# RoboSkinRev1.net
KiCad netlist of a schematic drawn in EAGLE
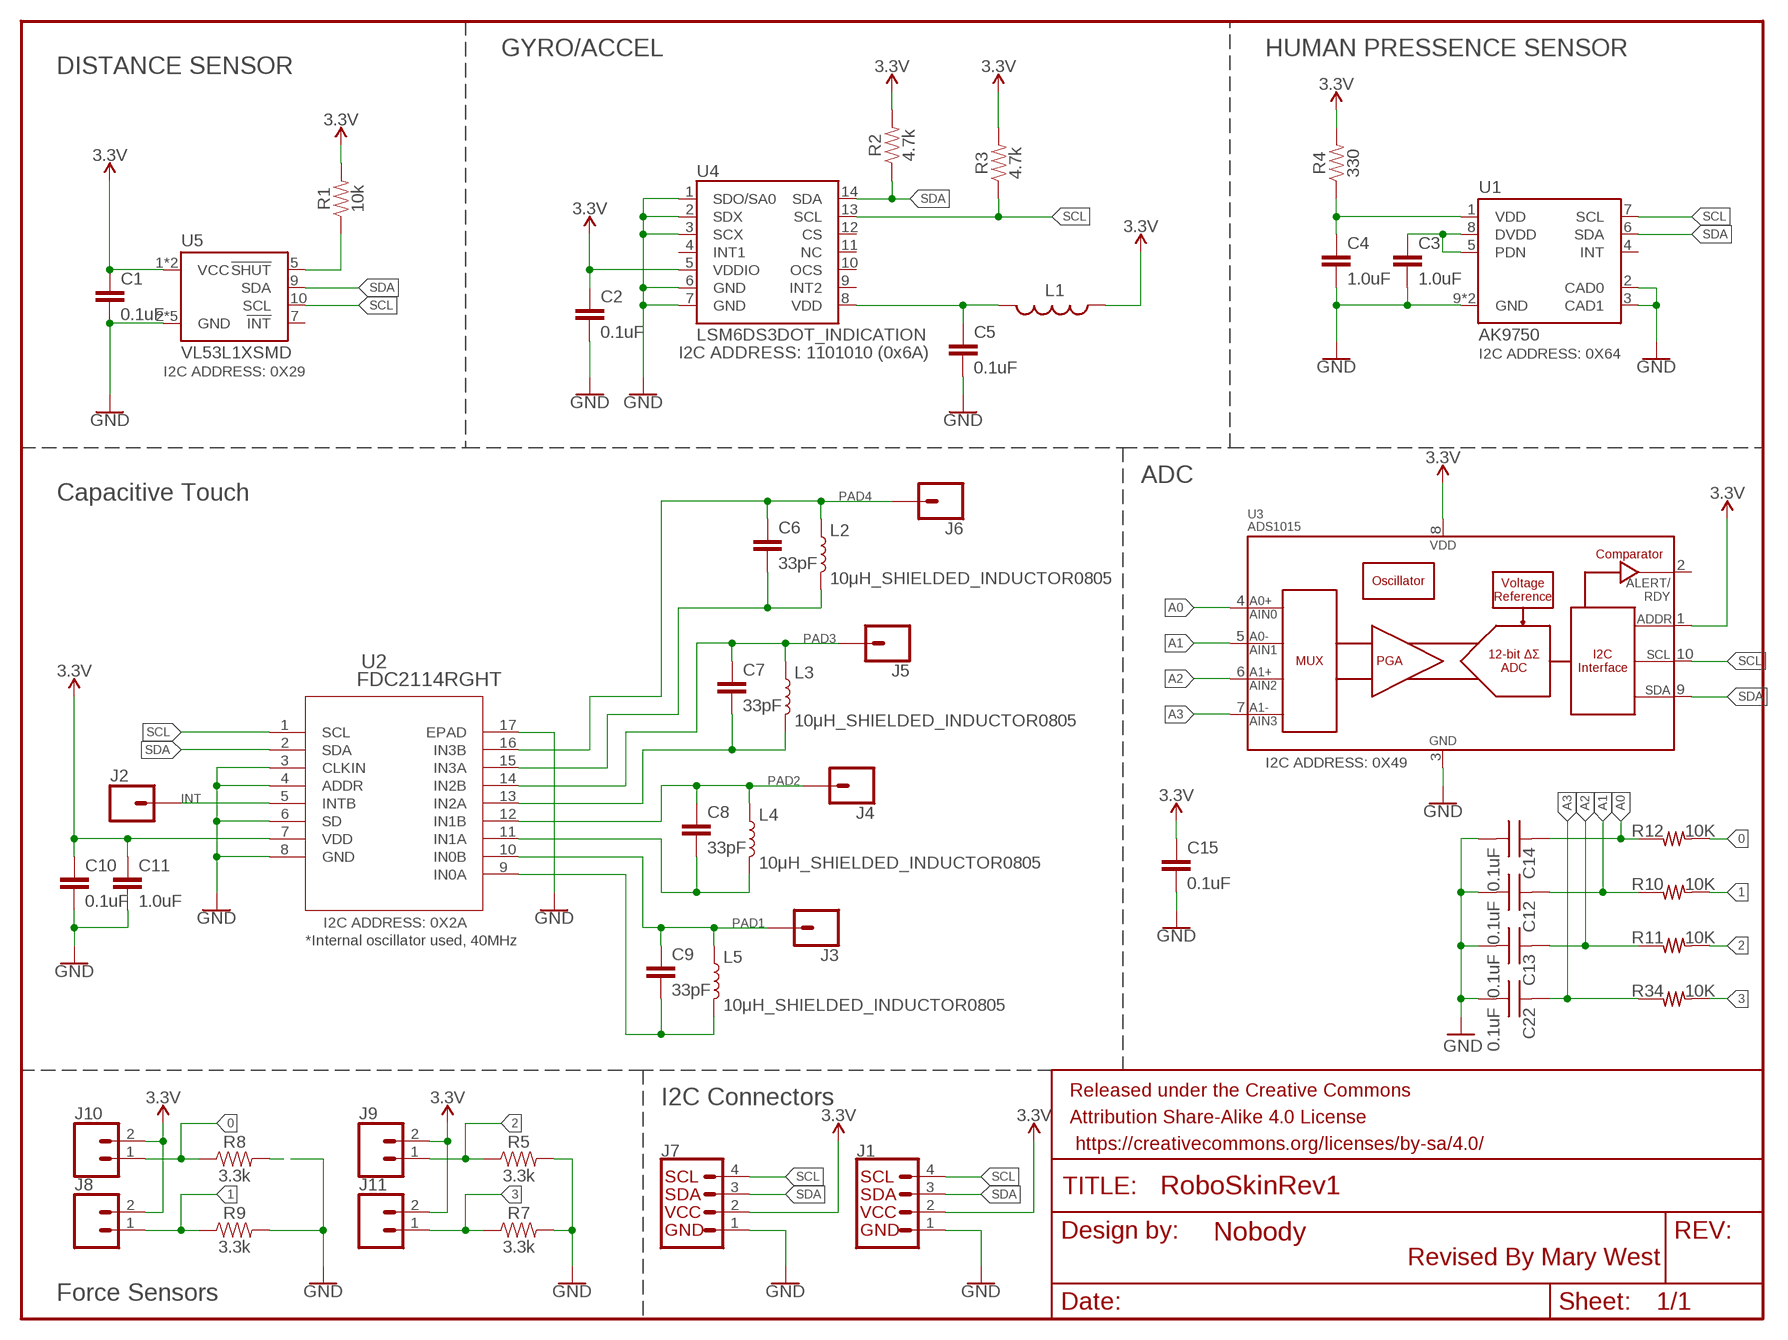
[diagram p0: schematic, sheet 1]

(export (version "E")
  (design (tool "Eeschema 10.0.6"))
  (components
    (comp (ref "C1")
      (value "0.1uF")
      (footprint "eagle-import:0603")
      (libsource (lib "eagle-import") (part "0.1UF-0603-25V-(+80/-20%)"))
    )
    (comp (ref "C2")
      (value "0.1uF")
      (footprint "eagle-import:0603")
      (libsource (lib "eagle-import") (part "0.1UF-0603-25V-(+80/-20%)"))
    )
    (comp (ref "C3")
      (value "1.0uF")
      (footprint "eagle-import:0603")
      (libsource (lib "eagle-import") (part "1.0UF-0603-16V-10%"))
    )
    (comp (ref "C4")
      (value "1.0uF")
      (footprint "eagle-import:0603")
      (libsource (lib "eagle-import") (part "1.0UF-0603-16V-10%"))
    )
    (comp (ref "C5")
      (value "0.1uF")
      (footprint "eagle-import:0603")
      (libsource (lib "eagle-import") (part "0.1UF-0603-25V-(+80/-20%)"))
    )
    (comp (ref "C6")
      (value "33pF")
      (footprint "eagle-import:0603")
      (libsource (lib "eagle-import") (part "33PF-0603-50V-5%"))
    )
    (comp (ref "C7")
      (value "33pF")
      (footprint "eagle-import:0603")
      (libsource (lib "eagle-import") (part "33PF-0603-50V-5%"))
    )
    (comp (ref "C8")
      (value "33pF")
      (footprint "eagle-import:0603")
      (libsource (lib "eagle-import") (part "33PF-0603-50V-5%"))
    )
    (comp (ref "C9")
      (value "33pF")
      (footprint "eagle-import:0603")
      (libsource (lib "eagle-import") (part "33PF-0603-50V-5%"))
    )
    (comp (ref "C10")
      (value "0.1uF")
      (footprint "eagle-import:0603")
      (libsource (lib "eagle-import") (part "0.1UF-0603-25V-(+80/-20%)"))
    )
    (comp (ref "C11")
      (value "1.0uF")
      (footprint "eagle-import:0603")
      (libsource (lib "eagle-import") (part "1.0UF-0603-16V-10%"))
    )
    (comp (ref "C12")
      (value "0.1uF")
      (footprint "eagle-import:0603_SILK")
      (fields (field (name "PARTNO") "GRM188R70J104KA01D"))
      (libsource (lib "eagle-import") (part "CAPACITORC_0603_SILK"))
    )
    (comp (ref "C13")
      (value "0.1uF")
      (footprint "eagle-import:0603_SILK")
      (fields (field (name "PARTNO") "GRM188R70J104KA01D"))
      (libsource (lib "eagle-import") (part "CAPACITORC_0603_SILK"))
    )
    (comp (ref "C14")
      (value "0.1uF")
      (footprint "eagle-import:0603_SILK")
      (fields (field (name "PARTNO") "GRM188R70J104KA01D"))
      (libsource (lib "eagle-import") (part "CAPACITORC_0603_SILK"))
    )
    (comp (ref "C15")
      (value "0.1uF")
      (footprint "eagle-import:0603")
      (libsource (lib "eagle-import") (part "0.1UF-0603-25V-(+80/-20%)"))
    )
    (comp (ref "C22")
      (value "0.1uF")
      (footprint "eagle-import:0603_SILK")
      (fields (field (name "PARTNO") "GRM188R70J104KA01D"))
      (libsource (lib "eagle-import") (part "CAPACITORC_0603_SILK"))
    )
    (comp (ref "FRAME1")
      (value "FRAME-LETTERNO_PACKAGE")
      (footprint "eagle-import:DUMMY")
      (fields (field (name "DESIGNER") "Nobody"))
      (libsource (lib "eagle-import") (part "FRAME-LETTERNO_PACKAGE"))
    )
    (comp (ref "J1")
      (value "QWIIC_CONNECTORJS-1MM")
      (footprint "eagle-import:1X04_1MM_RA")
      (libsource (lib "eagle-import") (part "QWIIC_CONNECTORJS-1MM"))
    )
    (comp (ref "J2")
      (value "CONN_01")
      (footprint "eagle-import:1X01")
      (libsource (lib "eagle-import") (part "CONN_01"))
    )
    (comp (ref "J3")
      (value "CONN_01")
      (footprint "eagle-import:1X01")
      (libsource (lib "eagle-import") (part "CONN_01"))
    )
    (comp (ref "J4")
      (value "CONN_01")
      (footprint "eagle-import:1X01")
      (libsource (lib "eagle-import") (part "CONN_01"))
    )
    (comp (ref "J5")
      (value "CONN_01")
      (footprint "eagle-import:1X01")
      (libsource (lib "eagle-import") (part "CONN_01"))
    )
    (comp (ref "J6")
      (value "CONN_01")
      (footprint "eagle-import:1X01")
      (libsource (lib "eagle-import") (part "CONN_01"))
    )
    (comp (ref "J7")
      (value "QWIIC_CONNECTORJS-1MM")
      (footprint "eagle-import:1X04_1MM_RA")
      (libsource (lib "eagle-import") (part "QWIIC_CONNECTORJS-1MM"))
    )
    (comp (ref "J8")
      (value "CONN_02")
      (footprint "eagle-import:1X02")
      (libsource (lib "eagle-import") (part "CONN_02"))
    )
    (comp (ref "J9")
      (value "CONN_02")
      (footprint "eagle-import:1X02")
      (libsource (lib "eagle-import") (part "CONN_02"))
    )
    (comp (ref "J10")
      (value "CONN_02")
      (footprint "eagle-import:1X02")
      (libsource (lib "eagle-import") (part "CONN_02"))
    )
    (comp (ref "J11")
      (value "CONN_02")
      (footprint "eagle-import:1X02")
      (libsource (lib "eagle-import") (part "CONN_02"))
    )
    (comp (ref "L1")
      (value "RES-07859")
      (footprint "eagle-import:0603")
      (libsource (lib "eagle-import") (part "INDUCTOR30OHM,1.8A"))
    )
    (comp (ref "L2")
      (value "10μH_SHIELDED_INDUCTOR0805")
      (footprint "eagle-import:0805")
      (libsource (lib "eagle-import") (part "10μH_SHIELDED_INDUCTOR0805"))
    )
    (comp (ref "L3")
      (value "10μH_SHIELDED_INDUCTOR0805")
      (footprint "eagle-import:0805")
      (libsource (lib "eagle-import") (part "10μH_SHIELDED_INDUCTOR0805"))
    )
    (comp (ref "L4")
      (value "10μH_SHIELDED_INDUCTOR0805")
      (footprint "eagle-import:0805")
      (libsource (lib "eagle-import") (part "10μH_SHIELDED_INDUCTOR0805"))
    )
    (comp (ref "L5")
      (value "10μH_SHIELDED_INDUCTOR0805")
      (footprint "eagle-import:0805")
      (libsource (lib "eagle-import") (part "10μH_SHIELDED_INDUCTOR0805"))
    )
    (comp (ref "R1")
      (value "10k")
      (footprint "eagle-import:0603")
      (libsource (lib "eagle-import") (part "10KOHM-0603-1/10W-1%"))
    )
    (comp (ref "R2")
      (value "4.7k")
      (footprint "eagle-import:0603")
      (libsource (lib "eagle-import") (part "4.7KOHM-0603-1/10W-1%"))
    )
    (comp (ref "R3")
      (value "4.7k")
      (footprint "eagle-import:0603")
      (libsource (lib "eagle-import") (part "4.7KOHM-0603-1/10W-1%"))
    )
    (comp (ref "R4")
      (value "330")
      (footprint "eagle-import:0603")
      (libsource (lib "eagle-import") (part "330OHM-0603-1/10W-1%"))
    )
    (comp (ref "R5")
      (value "3.3k")
      (footprint "eagle-import:0603")
      (libsource (lib "eagle-import") (part "3.3KOHM-0603-1/10W-1%"))
    )
    (comp (ref "R7")
      (value "3.3k")
      (footprint "eagle-import:0603")
      (libsource (lib "eagle-import") (part "3.3KOHM-0603-1/10W-1%"))
    )
    (comp (ref "R8")
      (value "3.3k")
      (footprint "eagle-import:0603")
      (libsource (lib "eagle-import") (part "3.3KOHM-0603-1/10W-1%"))
    )
    (comp (ref "R9")
      (value "3.3k")
      (footprint "eagle-import:0603")
      (libsource (lib "eagle-import") (part "3.3KOHM-0603-1/10W-1%"))
    )
    (comp (ref "R10")
      (value "10K")
      (footprint "eagle-import:0603_SILK")
      (fields (field (name "PARTNO") "CR0603-FX-1002ELF"))
      (libsource (lib "eagle-import") (part "RESISTORR_0603_SILK"))
    )
    (comp (ref "R11")
      (value "10K")
      (footprint "eagle-import:0603_SILK")
      (fields (field (name "PARTNO") "CR0603-FX-1002ELF"))
      (libsource (lib "eagle-import") (part "RESISTORR_0603_SILK"))
    )
    (comp (ref "R12")
      (value "10K")
      (footprint "eagle-import:0603_SILK")
      (fields (field (name "PARTNO") "CR0603-FX-1002ELF"))
      (libsource (lib "eagle-import") (part "RESISTORR_0603_SILK"))
    )
    (comp (ref "R34")
      (value "10K")
      (footprint "eagle-import:0603_SILK")
      (fields (field (name "PARTNO") "CR0603-FX-1002ELF"))
      (libsource (lib "eagle-import") (part "RESISTORR_0603_SILK"))
    )
    (comp (ref "U1")
      (value "AK9750")
      (footprint "eagle-import:SON10")
      (libsource (lib "eagle-import") (part "AK9750"))
    )
    (comp (ref "U2")
      (value "FDC2114RGHT")
      (footprint "eagle-import:RGH16")
      (fields (field (name "COPYRIGHT") "Copyright (C) 2018 Accelerated Designs. All rights reserved"))
      (libsource (lib "eagle-import") (part "FDC2114RGHT"))
    )
    (comp (ref "U3")
      (value "ADS1015")
      (footprint "eagle-import:MSOP10")
      (libsource (lib "eagle-import") (part "ADS1015"))
    )
    (comp (ref "U4")
      (value "LSM6DS3DOT_INDICATION")
      (footprint "eagle-import:LGA14L_DOT_INDICATOR")
      (libsource (lib "eagle-import") (part "LSM6DS3DOT_INDICATION"))
    )
    (comp (ref "U5")
      (value "VL53L1XSMD")
      (footprint "eagle-import:VL53L1X")
      (libsource (lib "eagle-import") (part "VL53L1XSMD"))
    )
  )
  (nets
    (net (code "1") (name "/INT") (class "Default")
      (node (ref "J2") (pin "1") (pinfunction "1_1") (pintype "passive"))
      (node (ref "U2") (pin "5") (pinfunction "INTB_5") (pintype "output"))
    )
    (net (code "2") (name "/PAD1") (class "Default")
      (node (ref "C9") (pin "1") (pinfunction "1_1") (pintype "passive"))
      (node (ref "J3") (pin "1") (pinfunction "1_1") (pintype "passive"))
      (node (ref "L5") (pin "1") (pinfunction "1_1") (pintype "passive"))
      (node (ref "U2") (pin "10") (pinfunction "IN0B_10") (pintype "input"))
    )
    (net (code "3") (name "/PAD2") (class "Default")
      (node (ref "C8") (pin "1") (pinfunction "1_1") (pintype "passive"))
      (node (ref "J4") (pin "1") (pinfunction "1_1") (pintype "passive"))
      (node (ref "L4") (pin "1") (pinfunction "1_1") (pintype "passive"))
      (node (ref "U2") (pin "12") (pinfunction "IN1B_12") (pintype "input"))
    )
    (net (code "4") (name "/PAD3") (class "Default")
      (node (ref "C7") (pin "1") (pinfunction "1_1") (pintype "passive"))
      (node (ref "J5") (pin "1") (pinfunction "1_1") (pintype "passive"))
      (node (ref "L3") (pin "1") (pinfunction "1_1") (pintype "passive"))
      (node (ref "U2") (pin "14") (pinfunction "IN2B_14") (pintype "input"))
    )
    (net (code "5") (name "/PAD4") (class "Default")
      (node (ref "C6") (pin "1") (pinfunction "1_1") (pintype "passive"))
      (node (ref "J6") (pin "1") (pinfunction "1_1") (pintype "passive"))
      (node (ref "L2") (pin "1") (pinfunction "1_1") (pintype "passive"))
      (node (ref "U2") (pin "16") (pinfunction "IN3B_16") (pintype "input"))
    )
    (net (code "6") (name "0") (class "Default")
      (node (ref "J10") (pin "1") (pinfunction "1_1") (pintype "passive"))
      (node (ref "R12") (pin "P2") (pinfunction "2_P2") (pintype "passive"))
      (node (ref "R8") (pin "1") (pinfunction "1_1") (pintype "passive"))
    )
    (net (code "7") (name "1") (class "Default")
      (node (ref "J8") (pin "1") (pinfunction "1_1") (pintype "passive"))
      (node (ref "R10") (pin "P2") (pinfunction "2_P2") (pintype "passive"))
      (node (ref "R9") (pin "1") (pinfunction "1_1") (pintype "passive"))
    )
    (net (code "8") (name "2") (class "Default")
      (node (ref "J9") (pin "1") (pinfunction "1_1") (pintype "passive"))
      (node (ref "R11") (pin "P2") (pinfunction "2_P2") (pintype "passive"))
      (node (ref "R5") (pin "1") (pinfunction "1_1") (pintype "passive"))
    )
    (net (code "9") (name "3") (class "Default")
      (node (ref "J11") (pin "1") (pinfunction "1_1") (pintype "passive"))
      (node (ref "R34") (pin "P2") (pinfunction "2_P2") (pintype "passive"))
      (node (ref "R7") (pin "1") (pinfunction "1_1") (pintype "passive"))
    )
    (net (code "10") (name "3.3V") (class "Default")
      (node (ref "C1") (pin "1") (pinfunction "1_1") (pintype "passive"))
      (node (ref "C10") (pin "1") (pinfunction "1_1") (pintype "passive"))
      (node (ref "C11") (pin "1") (pinfunction "1_1") (pintype "passive"))
      (node (ref "C15") (pin "1") (pinfunction "1_1") (pintype "passive"))
      (node (ref "C2") (pin "1") (pinfunction "1_1") (pintype "passive"))
      (node (ref "J1") (pin "2") (pinfunction "VCC_2") (pintype "power_in"))
      (node (ref "J10") (pin "2") (pinfunction "2_2") (pintype "passive"))
      (node (ref "J11") (pin "2") (pinfunction "2_2") (pintype "passive"))
      (node (ref "J7") (pin "2") (pinfunction "VCC_2") (pintype "power_in"))
      (node (ref "J8") (pin "2") (pinfunction "2_2") (pintype "passive"))
      (node (ref "J9") (pin "2") (pinfunction "2_2") (pintype "passive"))
      (node (ref "L1") (pin "1") (pinfunction "1_1") (pintype "passive"))
      (node (ref "R1") (pin "2") (pinfunction "2_2") (pintype "passive"))
      (node (ref "R2") (pin "2") (pinfunction "2_2") (pintype "passive"))
      (node (ref "R3") (pin "2") (pinfunction "2_2") (pintype "passive"))
      (node (ref "R4") (pin "2") (pinfunction "2_2") (pintype "passive"))
      (node (ref "U2") (pin "7") (pinfunction "VDD_7") (pintype "power_in"))
      (node (ref "U3") (pin "1") (pinfunction "ADDR_1") (pintype "bidirectional"))
      (node (ref "U3") (pin "8") (pinfunction "VDD_8") (pintype "bidirectional"))
      (node (ref "U4") (pin "5") (pinfunction "VDDIO_5") (pintype "bidirectional"))
      (node (ref "U5") (pin "1") (pinfunction "VCC_1") (pintype "bidirectional"))
      (node (ref "U5") (pin "11") (pinfunction "VCC_11") (pintype "bidirectional"))
    )
    (net (code "11") (name "A0") (class "Default")
      (node (ref "C14") (pin "P1") (pinfunction "1_P1") (pintype "passive"))
      (node (ref "R12") (pin "P1") (pinfunction "1_P1") (pintype "passive"))
      (node (ref "U3") (pin "4") (pinfunction "AIN0_4") (pintype "bidirectional"))
    )
    (net (code "12") (name "A1") (class "Default")
      (node (ref "C12") (pin "P1") (pinfunction "1_P1") (pintype "passive"))
      (node (ref "R10") (pin "P1") (pinfunction "1_P1") (pintype "passive"))
      (node (ref "U3") (pin "5") (pinfunction "AIN1_5") (pintype "bidirectional"))
    )
    (net (code "13") (name "A2") (class "Default")
      (node (ref "C13") (pin "P1") (pinfunction "1_P1") (pintype "passive"))
      (node (ref "R11") (pin "P1") (pinfunction "1_P1") (pintype "passive"))
      (node (ref "U3") (pin "6") (pinfunction "AIN2_6") (pintype "bidirectional"))
    )
    (net (code "14") (name "A3") (class "Default")
      (node (ref "C22") (pin "P1") (pinfunction "1_P1") (pintype "passive"))
      (node (ref "R34") (pin "P1") (pinfunction "1_P1") (pintype "passive"))
      (node (ref "U3") (pin "7") (pinfunction "AIN3_7") (pintype "bidirectional"))
    )
    (net (code "15") (name "GND") (class "Default")
      (node (ref "C1") (pin "2") (pinfunction "2_2") (pintype "passive"))
      (node (ref "C10") (pin "2") (pinfunction "2_2") (pintype "passive"))
      (node (ref "C11") (pin "2") (pinfunction "2_2") (pintype "passive"))
      (node (ref "C12") (pin "P2") (pinfunction "2_P2") (pintype "passive"))
      (node (ref "C13") (pin "P2") (pinfunction "2_P2") (pintype "passive"))
      (node (ref "C14") (pin "P2") (pinfunction "2_P2") (pintype "passive"))
      (node (ref "C15") (pin "2") (pinfunction "2_2") (pintype "passive"))
      (node (ref "C2") (pin "2") (pinfunction "2_2") (pintype "passive"))
      (node (ref "C22") (pin "P2") (pinfunction "2_P2") (pintype "passive"))
      (node (ref "C3") (pin "2") (pinfunction "2_2") (pintype "passive"))
      (node (ref "C4") (pin "2") (pinfunction "2_2") (pintype "passive"))
      (node (ref "C5") (pin "2") (pinfunction "2_2") (pintype "passive"))
      (node (ref "J1") (pin "1") (pinfunction "GND_1") (pintype "power_in"))
      (node (ref "J7") (pin "1") (pinfunction "GND_1") (pintype "power_in"))
      (node (ref "R5") (pin "2") (pinfunction "2_2") (pintype "passive"))
      (node (ref "R7") (pin "2") (pinfunction "2_2") (pintype "passive"))
      (node (ref "R8") (pin "2") (pinfunction "2_2") (pintype "passive"))
      (node (ref "R9") (pin "2") (pinfunction "2_2") (pintype "passive"))
      (node (ref "U1") (pin "10") (pinfunction "GND_10") (pintype "bidirectional"))
      (node (ref "U1") (pin "2") (pinfunction "CAD0_2") (pintype "bidirectional"))
      (node (ref "U1") (pin "3") (pinfunction "CAD1_3") (pintype "bidirectional"))
      (node (ref "U1") (pin "9") (pinfunction "GND_9") (pintype "bidirectional"))
      (node (ref "U2") (pin "17") (pinfunction "EPAD_17") (pintype "passive"))
      (node (ref "U2") (pin "3") (pinfunction "CLKIN_3") (pintype "input"))
      (node (ref "U2") (pin "4") (pinfunction "ADDR_4") (pintype "input"))
      (node (ref "U2") (pin "6") (pinfunction "SD_6") (pintype "input"))
      (node (ref "U2") (pin "8") (pinfunction "GND_8") (pintype "power_in"))
      (node (ref "U3") (pin "3") (pinfunction "VSS_3") (pintype "bidirectional"))
      (node (ref "U4") (pin "1") (pinfunction "SDO/SA0_1") (pintype "bidirectional"))
      (node (ref "U4") (pin "2") (pinfunction "SDX_2") (pintype "bidirectional"))
      (node (ref "U4") (pin "3") (pinfunction "SCX_3") (pintype "bidirectional"))
      (node (ref "U4") (pin "6") (pinfunction "GND_6") (pintype "bidirectional"))
      (node (ref "U4") (pin "7") (pinfunction "GND_7") (pintype "bidirectional"))
      (node (ref "U5") (pin "12") (pinfunction "GND_12") (pintype "bidirectional"))
      (node (ref "U5") (pin "2") (pinfunction "GND_2") (pintype "bidirectional"))
      (node (ref "U5") (pin "3") (pinfunction "GND_3") (pintype "bidirectional"))
      (node (ref "U5") (pin "4") (pinfunction "GND_4") (pintype "bidirectional"))
      (node (ref "U5") (pin "6") (pinfunction "GND_6") (pintype "bidirectional"))
    )
    (net (code "16") (name "Net-(U1-DVDD)") (class "Default")
      (node (ref "C3") (pin "1") (pinfunction "1_1") (pintype "passive"))
      (node (ref "U1") (pin "5") (pinfunction "PDN_5") (pintype "bidirectional"))
      (node (ref "U1") (pin "8") (pinfunction "DVDD_8") (pintype "bidirectional"))
    )
    (net (code "17") (name "Net-(U1-VDD)") (class "Default")
      (node (ref "C4") (pin "1") (pinfunction "1_1") (pintype "passive"))
      (node (ref "R4") (pin "1") (pinfunction "1_1") (pintype "passive"))
      (node (ref "U1") (pin "1") (pinfunction "VDD_1") (pintype "bidirectional"))
    )
    (net (code "18") (name "Net-(U2-IN0A)") (class "Default")
      (node (ref "C9") (pin "2") (pinfunction "2_2") (pintype "passive"))
      (node (ref "L5") (pin "2") (pinfunction "2_2") (pintype "passive"))
      (node (ref "U2") (pin "9") (pinfunction "IN0A_9") (pintype "input"))
    )
    (net (code "19") (name "Net-(U2-IN1A)") (class "Default")
      (node (ref "C8") (pin "2") (pinfunction "2_2") (pintype "passive"))
      (node (ref "L4") (pin "2") (pinfunction "2_2") (pintype "passive"))
      (node (ref "U2") (pin "11") (pinfunction "IN1A_11") (pintype "input"))
    )
    (net (code "20") (name "Net-(U2-IN2A)") (class "Default")
      (node (ref "C7") (pin "2") (pinfunction "2_2") (pintype "passive"))
      (node (ref "L3") (pin "2") (pinfunction "2_2") (pintype "passive"))
      (node (ref "U2") (pin "13") (pinfunction "IN2A_13") (pintype "input"))
    )
    (net (code "21") (name "Net-(U2-IN3A)") (class "Default")
      (node (ref "C6") (pin "2") (pinfunction "2_2") (pintype "passive"))
      (node (ref "L2") (pin "2") (pinfunction "2_2") (pintype "passive"))
      (node (ref "U2") (pin "15") (pinfunction "IN3A_15") (pintype "input"))
    )
    (net (code "22") (name "Net-(U4-VDD)") (class "Default")
      (node (ref "C5") (pin "1") (pinfunction "1_1") (pintype "passive"))
      (node (ref "L1") (pin "2") (pinfunction "2_2") (pintype "passive"))
      (node (ref "U4") (pin "8") (pinfunction "VDD_8") (pintype "bidirectional"))
    )
    (net (code "23") (name "Net-(U5-~{SHUT})") (class "Default")
      (node (ref "R1") (pin "1") (pinfunction "1_1") (pintype "passive"))
      (node (ref "U5") (pin "5") (pinfunction "~{SHUT}_5") (pintype "bidirectional"))
    )
    (net (code "24") (name "SCL") (class "Default")
      (node (ref "J1") (pin "4") (pinfunction "SCL_4") (pintype "passive"))
      (node (ref "J7") (pin "4") (pinfunction "SCL_4") (pintype "passive"))
      (node (ref "R3") (pin "1") (pinfunction "1_1") (pintype "passive"))
      (node (ref "U1") (pin "7") (pinfunction "SCL_7") (pintype "bidirectional"))
      (node (ref "U2") (pin "1") (pinfunction "SCL_1") (pintype "input"))
      (node (ref "U3") (pin "10") (pinfunction "SCL_10") (pintype "bidirectional"))
      (node (ref "U4") (pin "13") (pinfunction "SCL_13") (pintype "bidirectional"))
      (node (ref "U5") (pin "10") (pinfunction "SCL_10") (pintype "bidirectional"))
    )
    (net (code "25") (name "SDA") (class "Default")
      (node (ref "J1") (pin "3") (pinfunction "SDA_3") (pintype "passive"))
      (node (ref "J7") (pin "3") (pinfunction "SDA_3") (pintype "passive"))
      (node (ref "R2") (pin "1") (pinfunction "1_1") (pintype "passive"))
      (node (ref "U1") (pin "6") (pinfunction "SDA_6") (pintype "bidirectional"))
      (node (ref "U2") (pin "2") (pinfunction "SDA_2") (pintype "bidirectional"))
      (node (ref "U3") (pin "9") (pinfunction "SDA_9") (pintype "bidirectional"))
      (node (ref "U4") (pin "14") (pinfunction "SDA_14") (pintype "bidirectional"))
      (node (ref "U5") (pin "9") (pinfunction "SDA_9") (pintype "bidirectional"))
    )
    (net (code "26") (name "unconnected-(U1-INT-Pad4)") (class "Default")
      (node (ref "U1") (pin "4") (pinfunction "INT_4") (pintype "bidirectional"))
    )
    (net (code "27") (name "unconnected-(U3-ALERT{slash}RDY-Pad2)") (class "Default")
      (node (ref "U3") (pin "2") (pinfunction "ALERT/RDY_2") (pintype "bidirectional"))
    )
    (net (code "28") (name "unconnected-(U4-CS-Pad12)") (class "Default")
      (node (ref "U4") (pin "12") (pinfunction "CS_12") (pintype "bidirectional"))
    )
    (net (code "29") (name "unconnected-(U4-INT1-Pad4)") (class "Default")
      (node (ref "U4") (pin "4") (pinfunction "INT1_4") (pintype "bidirectional"))
    )
    (net (code "30") (name "unconnected-(U4-INT2-Pad9)") (class "Default")
      (node (ref "U4") (pin "9") (pinfunction "INT2_9") (pintype "bidirectional"))
    )
    (net (code "31") (name "unconnected-(U4-NC-Pad11)") (class "Default")
      (node (ref "U4") (pin "11") (pinfunction "NC_11") (pintype "bidirectional"))
    )
    (net (code "32") (name "unconnected-(U4-OCS-Pad10)") (class "Default")
      (node (ref "U4") (pin "10") (pinfunction "OCS_10") (pintype "bidirectional"))
    )
    (net (code "33") (name "unconnected-(U5-~{INT}-Pad7)") (class "Default")
      (node (ref "U5") (pin "7") (pinfunction "~{INT}_7") (pintype "bidirectional"))
    )
  )
)
